# madaq_filter_panel_JAV.net
KiCad netlist of a schematic drawn in EAGLE
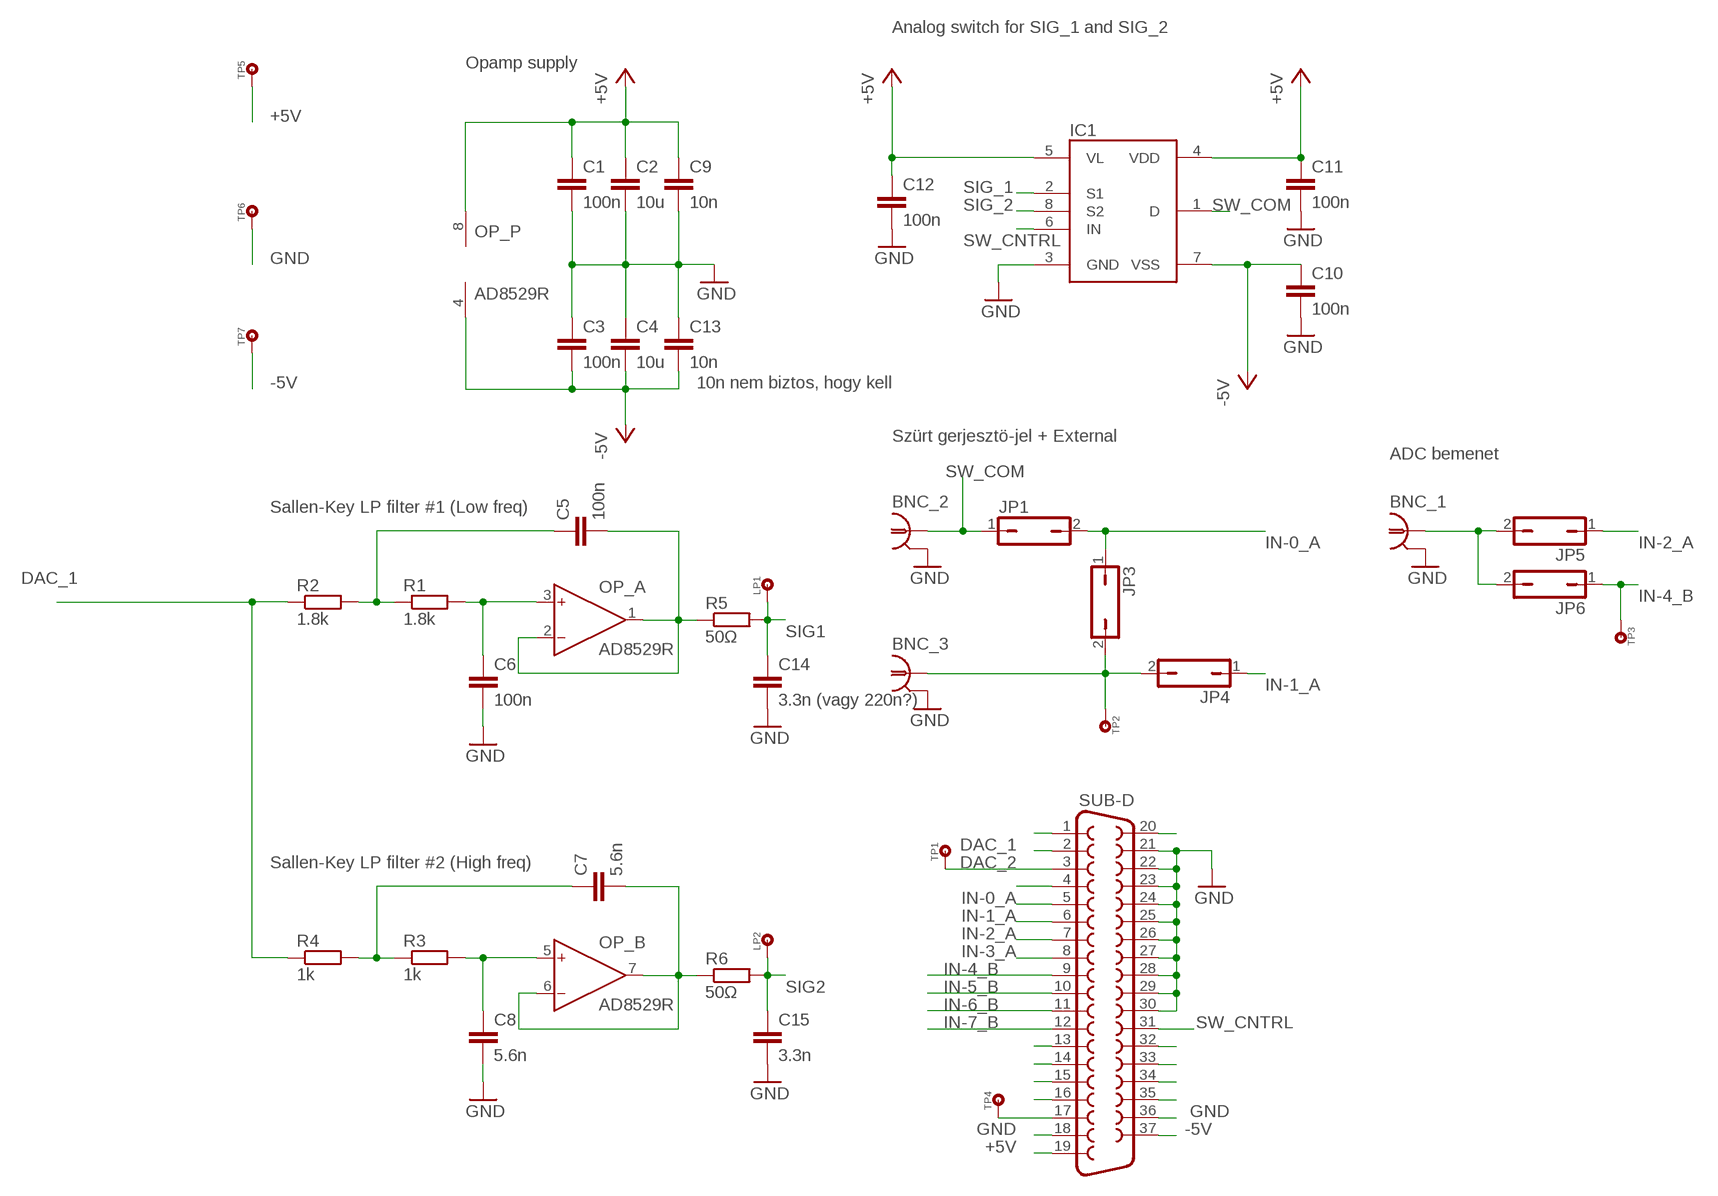
[diagram p0: schematic, sheet 1]

(export (version "E")
  (design (tool "Eeschema 10.0.6"))
  (components
    (comp (ref "BNC_1")
      (value "BNC-ISOL-90I")
      (footprint "eagle-import:BNCPCB90I")
      (libsource (lib "eagle-import") (part "BNC-ISOL-90I"))
    )
    (comp (ref "BNC_2")
      (value "BNC-ISOL-90I")
      (footprint "eagle-import:BNCPCB90I")
      (libsource (lib "eagle-import") (part "BNC-ISOL-90I"))
    )
    (comp (ref "BNC_3")
      (value "BNC-ISOL-90I")
      (footprint "eagle-import:BNCPCB90I")
      (libsource (lib "eagle-import") (part "BNC-ISOL-90I"))
    )
    (comp (ref "C1")
      (value "100n")
      (footprint "eagle-import:C1206")
      (libsource (lib "eagle-import") (part "C1206"))
    )
    (comp (ref "C2")
      (value "10u")
      (footprint "eagle-import:C1206")
      (libsource (lib "eagle-import") (part "C1206"))
    )
    (comp (ref "C3")
      (value "100n")
      (footprint "eagle-import:C1206")
      (libsource (lib "eagle-import") (part "C1206"))
    )
    (comp (ref "C4")
      (value "10u")
      (footprint "eagle-import:C1206")
      (libsource (lib "eagle-import") (part "C1206"))
    )
    (comp (ref "C5")
      (value "100n")
      (footprint "eagle-import:C1206")
      (libsource (lib "eagle-import") (part "C1206"))
    )
    (comp (ref "C6")
      (value "100n")
      (footprint "eagle-import:C1206")
      (libsource (lib "eagle-import") (part "C1206"))
    )
    (comp (ref "C7")
      (value "5.6n")
      (footprint "eagle-import:C1206")
      (libsource (lib "eagle-import") (part "C1206"))
    )
    (comp (ref "C8")
      (value "5.6n")
      (footprint "eagle-import:C1206")
      (libsource (lib "eagle-import") (part "C1206"))
    )
    (comp (ref "C9")
      (value "10n")
      (footprint "eagle-import:C1206")
      (libsource (lib "eagle-import") (part "C1206"))
    )
    (comp (ref "C10")
      (value "100n")
      (footprint "eagle-import:C1206")
      (libsource (lib "eagle-import") (part "C1206"))
    )
    (comp (ref "C11")
      (value "100n")
      (footprint "eagle-import:C1206")
      (libsource (lib "eagle-import") (part "C1206"))
    )
    (comp (ref "C12")
      (value "100n")
      (footprint "eagle-import:C1206")
      (libsource (lib "eagle-import") (part "C1206"))
    )
    (comp (ref "C13")
      (value "10n")
      (footprint "eagle-import:C1206")
      (libsource (lib "eagle-import") (part "C1206"))
    )
    (comp (ref "C14")
      (value "3.3n (vagy 220n?)")
      (footprint "eagle-import:C1206")
      (libsource (lib "eagle-import") (part "C1206"))
    )
    (comp (ref "C15")
      (value "3.3n")
      (footprint "eagle-import:C1206")
      (libsource (lib "eagle-import") (part "C1206"))
    )
    (comp (ref "IC1")
      (value "ADG419BR")
      (footprint "eagle-import:SO08")
      (libsource (lib "eagle-import") (part "ADG419BR"))
    )
    (comp (ref "JP1")
      (value "JP1Q")
      (footprint "eagle-import:JP1")
      (libsource (lib "eagle-import") (part "JP1Q"))
    )
    (comp (ref "JP3")
      (value "JP1Q")
      (footprint "eagle-import:JP1")
      (libsource (lib "eagle-import") (part "JP1Q"))
    )
    (comp (ref "JP4")
      (value "JP1Q")
      (footprint "eagle-import:JP1")
      (libsource (lib "eagle-import") (part "JP1Q"))
    )
    (comp (ref "JP5")
      (value "JP1Q")
      (footprint "eagle-import:JP1")
      (libsource (lib "eagle-import") (part "JP1Q"))
    )
    (comp (ref "JP6")
      (value "JP1Q")
      (footprint "eagle-import:JP1")
      (libsource (lib "eagle-import") (part "JP1Q"))
    )
    (comp (ref "LP1")
      (value "TP")
      (footprint "eagle-import:JP1")
      (libsource (lib "eagle-import") (part "TP"))
    )
    (comp (ref "LP2")
      (value "TP")
      (footprint "eagle-import:JP1")
      (libsource (lib "eagle-import") (part "TP"))
    )
    (comp (ref "OP_")
      (value "AD8529R")
      (footprint "eagle-import:SO8")
      (fields (field (name "MF") "ALTERA CORPORATION") (field (name "MPN") "AD8529ARZ"))
      (libsource (lib "eagle-import") (part "AD8529R"))
    )
    (comp (ref "R1")
      (value "1.8k")
      (footprint "eagle-import:R1206")
      (libsource (lib "eagle-import") (part "R1206"))
    )
    (comp (ref "R2")
      (value "1.8k")
      (footprint "eagle-import:R1206")
      (libsource (lib "eagle-import") (part "R1206"))
    )
    (comp (ref "R3")
      (value "1k")
      (footprint "eagle-import:R1206")
      (libsource (lib "eagle-import") (part "R1206"))
    )
    (comp (ref "R4")
      (value "1k")
      (footprint "eagle-import:R1206")
      (libsource (lib "eagle-import") (part "R1206"))
    )
    (comp (ref "R5")
      (value "50Ω")
      (footprint "eagle-import:R1206")
      (libsource (lib "eagle-import") (part "R1206"))
    )
    (comp (ref "R6")
      (value "50Ω")
      (footprint "eagle-import:R1206")
      (libsource (lib "eagle-import") (part "R1206"))
    )
    (comp (ref "SUB-D")
      (value "F37HP")
      (footprint "eagle-import:F37HP")
      (libsource (lib "eagle-import") (part "F37HP"))
    )
    (comp (ref "TP1")
      (value "TP")
      (footprint "eagle-import:JP1")
      (libsource (lib "eagle-import") (part "TP"))
    )
    (comp (ref "TP2")
      (value "TP")
      (footprint "eagle-import:JP1")
      (libsource (lib "eagle-import") (part "TP"))
    )
    (comp (ref "TP3")
      (value "TP")
      (footprint "eagle-import:JP1")
      (libsource (lib "eagle-import") (part "TP"))
    )
    (comp (ref "TP4")
      (value "TP")
      (footprint "eagle-import:JP1")
      (libsource (lib "eagle-import") (part "TP"))
    )
    (comp (ref "TP5")
      (value "TP")
      (footprint "eagle-import:JP1")
      (libsource (lib "eagle-import") (part "TP"))
    )
    (comp (ref "TP6")
      (value "TP")
      (footprint "eagle-import:JP1")
      (libsource (lib "eagle-import") (part "TP"))
    )
    (comp (ref "TP7")
      (value "TP")
      (footprint "eagle-import:JP1")
      (libsource (lib "eagle-import") (part "TP"))
    )
  )
  (nets
    (net (code "1") (name "+5V") (class "Default")
      (node (ref "C1") (pin "2") (pinfunction "2_2") (pintype "passive"))
      (node (ref "C11") (pin "2") (pinfunction "2_2") (pintype "passive"))
      (node (ref "C12") (pin "2") (pinfunction "2_2") (pintype "passive"))
      (node (ref "C2") (pin "2") (pinfunction "2_2") (pintype "passive"))
      (node (ref "C9") (pin "2") (pinfunction "2_2") (pintype "passive"))
      (node (ref "IC1") (pin "4") (pinfunction "VDD_4") (pintype "power_in"))
      (node (ref "IC1") (pin "5") (pinfunction "VL_5") (pintype "power_in"))
      (node (ref "OP_") (pin "8") (pinfunction "V+_8") (pintype "power_in"))
      (node (ref "SUB-D") (pin "19") (pinfunction "19_19") (pintype "passive"))
      (node (ref "TP5") (pin "1") (pinfunction "1_1") (pintype "bidirectional"))
    )
    (net (code "2") (name "-5V") (class "Default")
      (node (ref "C10") (pin "2") (pinfunction "2_2") (pintype "passive"))
      (node (ref "C13") (pin "1") (pinfunction "1_1") (pintype "passive"))
      (node (ref "C3") (pin "1") (pinfunction "1_1") (pintype "passive"))
      (node (ref "C4") (pin "1") (pinfunction "1_1") (pintype "passive"))
      (node (ref "IC1") (pin "7") (pinfunction "VSS_7") (pintype "power_in"))
      (node (ref "OP_") (pin "4") (pinfunction "V-_4") (pintype "power_in"))
      (node (ref "SUB-D") (pin "37") (pinfunction "37_37") (pintype "passive"))
      (node (ref "TP7") (pin "1") (pinfunction "1_1") (pintype "bidirectional"))
    )
    (net (code "3") (name "/DAC_1") (class "Default")
      (node (ref "R2") (pin "1") (pinfunction "1_1") (pintype "passive"))
      (node (ref "R4") (pin "1") (pinfunction "1_1") (pintype "passive"))
      (node (ref "SUB-D") (pin "2") (pinfunction "2_2") (pintype "passive"))
    )
    (net (code "4") (name "/DAC_2") (class "Default")
      (node (ref "SUB-D") (pin "3") (pinfunction "3_3") (pintype "passive"))
      (node (ref "TP1") (pin "1") (pinfunction "1_1") (pintype "bidirectional"))
    )
    (net (code "5") (name "/IN-0_A") (class "Default")
      (node (ref "JP1") (pin "2") (pinfunction "2_2") (pintype "passive"))
      (node (ref "JP3") (pin "1") (pinfunction "1_1") (pintype "passive"))
      (node (ref "SUB-D") (pin "5") (pinfunction "5_5") (pintype "passive"))
    )
    (net (code "6") (name "/IN-1_A") (class "Default")
      (node (ref "JP4") (pin "1") (pinfunction "1_1") (pintype "passive"))
      (node (ref "SUB-D") (pin "6") (pinfunction "6_6") (pintype "passive"))
    )
    (net (code "7") (name "/IN-2_A") (class "Default")
      (node (ref "JP5") (pin "1") (pinfunction "1_1") (pintype "passive"))
      (node (ref "SUB-D") (pin "7") (pinfunction "7_7") (pintype "passive"))
    )
    (net (code "8") (name "/IN-3_A") (class "Default")
      (node (ref "SUB-D") (pin "8") (pinfunction "8_8") (pintype "passive"))
    )
    (net (code "9") (name "/IN-4_B") (class "Default")
      (node (ref "JP6") (pin "1") (pinfunction "1_1") (pintype "passive"))
      (node (ref "SUB-D") (pin "9") (pinfunction "9_9") (pintype "passive"))
      (node (ref "TP3") (pin "1") (pinfunction "1_1") (pintype "bidirectional"))
    )
    (net (code "10") (name "/IN-5_B") (class "Default")
      (node (ref "SUB-D") (pin "10") (pinfunction "10_10") (pintype "passive"))
    )
    (net (code "11") (name "/IN-6_B") (class "Default")
      (node (ref "SUB-D") (pin "11") (pinfunction "11_11") (pintype "passive"))
    )
    (net (code "12") (name "/IN-7_B") (class "Default")
      (node (ref "SUB-D") (pin "12") (pinfunction "12_12") (pintype "passive"))
    )
    (net (code "13") (name "/SIG1") (class "Default")
      (node (ref "C14") (pin "2") (pinfunction "2_2") (pintype "passive"))
      (node (ref "LP1") (pin "1") (pinfunction "1_1") (pintype "bidirectional"))
      (node (ref "R5") (pin "2") (pinfunction "2_2") (pintype "passive"))
    )
    (net (code "14") (name "/SIG2") (class "Default")
      (node (ref "C15") (pin "2") (pinfunction "2_2") (pintype "passive"))
      (node (ref "LP2") (pin "1") (pinfunction "1_1") (pintype "bidirectional"))
      (node (ref "R6") (pin "2") (pinfunction "2_2") (pintype "passive"))
    )
    (net (code "15") (name "/SIG_1") (class "Default")
      (node (ref "IC1") (pin "2") (pinfunction "S1_2") (pintype "bidirectional"))
    )
    (net (code "16") (name "/SIG_2") (class "Default")
      (node (ref "IC1") (pin "8") (pinfunction "S2_8") (pintype "bidirectional"))
    )
    (net (code "17") (name "/SW_CNTRL") (class "Default")
      (node (ref "IC1") (pin "6") (pinfunction "IN_6") (pintype "input"))
      (node (ref "SUB-D") (pin "31") (pinfunction "31_31") (pintype "passive"))
    )
    (net (code "18") (name "/SW_COM") (class "Default")
      (node (ref "BNC_2") (pin "SIGNAL") (pinfunction "SIGNAL_SIGNAL") (pintype "passive"))
      (node (ref "IC1") (pin "1") (pinfunction "D_1") (pintype "bidirectional"))
      (node (ref "JP1") (pin "1") (pinfunction "1_1") (pintype "passive"))
    )
    (net (code "19") (name "GND") (class "Default")
      (node (ref "BNC_1") (pin "SHIELD") (pinfunction "SHIELD_SHIELD") (pintype "passive"))
      (node (ref "BNC_2") (pin "SHIELD") (pinfunction "SHIELD_SHIELD") (pintype "passive"))
      (node (ref "BNC_3") (pin "SHIELD") (pinfunction "SHIELD_SHIELD") (pintype "passive"))
      (node (ref "C1") (pin "1") (pinfunction "1_1") (pintype "passive"))
      (node (ref "C10") (pin "1") (pinfunction "1_1") (pintype "passive"))
      (node (ref "C11") (pin "1") (pinfunction "1_1") (pintype "passive"))
      (node (ref "C12") (pin "1") (pinfunction "1_1") (pintype "passive"))
      (node (ref "C13") (pin "2") (pinfunction "2_2") (pintype "passive"))
      (node (ref "C14") (pin "1") (pinfunction "1_1") (pintype "passive"))
      (node (ref "C15") (pin "1") (pinfunction "1_1") (pintype "passive"))
      (node (ref "C2") (pin "1") (pinfunction "1_1") (pintype "passive"))
      (node (ref "C3") (pin "2") (pinfunction "2_2") (pintype "passive"))
      (node (ref "C4") (pin "2") (pinfunction "2_2") (pintype "passive"))
      (node (ref "C6") (pin "1") (pinfunction "1_1") (pintype "passive"))
      (node (ref "C8") (pin "1") (pinfunction "1_1") (pintype "passive"))
      (node (ref "C9") (pin "1") (pinfunction "1_1") (pintype "passive"))
      (node (ref "IC1") (pin "3") (pinfunction "GND_3") (pintype "power_in"))
      (node (ref "SUB-D") (pin "18") (pinfunction "18_18") (pintype "passive"))
      (node (ref "SUB-D") (pin "21") (pinfunction "21_21") (pintype "passive"))
      (node (ref "SUB-D") (pin "22") (pinfunction "22_22") (pintype "passive"))
      (node (ref "SUB-D") (pin "23") (pinfunction "23_23") (pintype "passive"))
      (node (ref "SUB-D") (pin "24") (pinfunction "24_24") (pintype "passive"))
      (node (ref "SUB-D") (pin "25") (pinfunction "25_25") (pintype "passive"))
      (node (ref "SUB-D") (pin "26") (pinfunction "26_26") (pintype "passive"))
      (node (ref "SUB-D") (pin "27") (pinfunction "27_27") (pintype "passive"))
      (node (ref "SUB-D") (pin "28") (pinfunction "28_28") (pintype "passive"))
      (node (ref "SUB-D") (pin "29") (pinfunction "29_29") (pintype "passive"))
      (node (ref "SUB-D") (pin "30") (pinfunction "30_30") (pintype "passive"))
      (node (ref "SUB-D") (pin "36") (pinfunction "36_36") (pintype "passive"))
      (node (ref "TP6") (pin "1") (pinfunction "1_1") (pintype "bidirectional"))
    )
    (net (code "20") (name "Net-(BNC_1-PadSIGNAL)") (class "Default")
      (node (ref "BNC_1") (pin "SIGNAL") (pinfunction "SIGNAL_SIGNAL") (pintype "passive"))
      (node (ref "JP5") (pin "2") (pinfunction "2_2") (pintype "passive"))
      (node (ref "JP6") (pin "2") (pinfunction "2_2") (pintype "passive"))
    )
    (net (code "21") (name "Net-(BNC_3-PadSIGNAL)") (class "Default")
      (node (ref "BNC_3") (pin "SIGNAL") (pinfunction "SIGNAL_SIGNAL") (pintype "passive"))
      (node (ref "JP3") (pin "2") (pinfunction "2_2") (pintype "passive"))
      (node (ref "JP4") (pin "2") (pinfunction "2_2") (pintype "passive"))
      (node (ref "TP2") (pin "1") (pinfunction "1_1") (pintype "bidirectional"))
    )
    (net (code "22") (name "Net-(C5-Pad2)") (class "Default")
      (node (ref "C5") (pin "2") (pinfunction "2_2") (pintype "passive"))
      (node (ref "R1") (pin "1") (pinfunction "1_1") (pintype "passive"))
      (node (ref "R2") (pin "2") (pinfunction "2_2") (pintype "passive"))
    )
    (net (code "23") (name "Net-(C7-Pad2)") (class "Default")
      (node (ref "C7") (pin "2") (pinfunction "2_2") (pintype "passive"))
      (node (ref "R3") (pin "1") (pinfunction "1_1") (pintype "passive"))
      (node (ref "R4") (pin "2") (pinfunction "2_2") (pintype "passive"))
    )
    (net (code "24") (name "Net-(OP_A-IN+)") (class "Default")
      (node (ref "C6") (pin "2") (pinfunction "2_2") (pintype "passive"))
      (node (ref "OP_") (pin "3") (pinfunction "IN+_3") (pintype "input"))
      (node (ref "R1") (pin "2") (pinfunction "2_2") (pintype "passive"))
    )
    (net (code "25") (name "Net-(OP_A-IN-)") (class "Default")
      (node (ref "C5") (pin "1") (pinfunction "1_1") (pintype "passive"))
      (node (ref "OP_") (pin "1") (pinfunction "OUT_1") (pintype "output"))
      (node (ref "OP_") (pin "2") (pinfunction "IN-_2") (pintype "input"))
      (node (ref "R5") (pin "1") (pinfunction "1_1") (pintype "passive"))
    )
    (net (code "26") (name "Net-(OP_B-IN+)") (class "Default")
      (node (ref "C8") (pin "2") (pinfunction "2_2") (pintype "passive"))
      (node (ref "OP_") (pin "5") (pinfunction "IN+_5") (pintype "input"))
      (node (ref "R3") (pin "2") (pinfunction "2_2") (pintype "passive"))
    )
    (net (code "27") (name "Net-(OP_B-IN-)") (class "Default")
      (node (ref "C7") (pin "1") (pinfunction "1_1") (pintype "passive"))
      (node (ref "OP_") (pin "6") (pinfunction "IN-_6") (pintype "input"))
      (node (ref "OP_") (pin "7") (pinfunction "OUT_7") (pintype "output"))
      (node (ref "R6") (pin "1") (pinfunction "1_1") (pintype "passive"))
    )
    (net (code "28") (name "Net-(SUB-D-Pad17)") (class "Default")
      (node (ref "SUB-D") (pin "17") (pinfunction "17_17") (pintype "passive"))
      (node (ref "TP4") (pin "1") (pinfunction "1_1") (pintype "bidirectional"))
    )
    (net (code "29") (name "unconnected-(SUB-D-Pad1)") (class "Default")
      (node (ref "SUB-D") (pin "1") (pinfunction "1_1") (pintype "passive"))
    )
    (net (code "30") (name "unconnected-(SUB-D-Pad4)") (class "Default")
      (node (ref "SUB-D") (pin "4") (pinfunction "4_4") (pintype "passive"))
    )
    (net (code "31") (name "unconnected-(SUB-D-Pad13)") (class "Default")
      (node (ref "SUB-D") (pin "13") (pinfunction "13_13") (pintype "passive"))
    )
    (net (code "32") (name "unconnected-(SUB-D-Pad14)") (class "Default")
      (node (ref "SUB-D") (pin "14") (pinfunction "14_14") (pintype "passive"))
    )
    (net (code "33") (name "unconnected-(SUB-D-Pad15)") (class "Default")
      (node (ref "SUB-D") (pin "15") (pinfunction "15_15") (pintype "passive"))
    )
    (net (code "34") (name "unconnected-(SUB-D-Pad16)") (class "Default")
      (node (ref "SUB-D") (pin "16") (pinfunction "16_16") (pintype "passive"))
    )
    (net (code "35") (name "unconnected-(SUB-D-Pad20)") (class "Default")
      (node (ref "SUB-D") (pin "20") (pinfunction "20_20") (pintype "passive"))
    )
    (net (code "36") (name "unconnected-(SUB-D-Pad32)") (class "Default")
      (node (ref "SUB-D") (pin "32") (pinfunction "32_32") (pintype "passive"))
    )
    (net (code "37") (name "unconnected-(SUB-D-Pad33)") (class "Default")
      (node (ref "SUB-D") (pin "33") (pinfunction "33_33") (pintype "passive"))
    )
    (net (code "38") (name "unconnected-(SUB-D-Pad34)") (class "Default")
      (node (ref "SUB-D") (pin "34") (pinfunction "34_34") (pintype "passive"))
    )
    (net (code "39") (name "unconnected-(SUB-D-Pad35)") (class "Default")
      (node (ref "SUB-D") (pin "35") (pinfunction "35_35") (pintype "passive"))
    )
  )
)
